# NuEVI.net
KiCad netlist of a schematic drawn in EAGLE
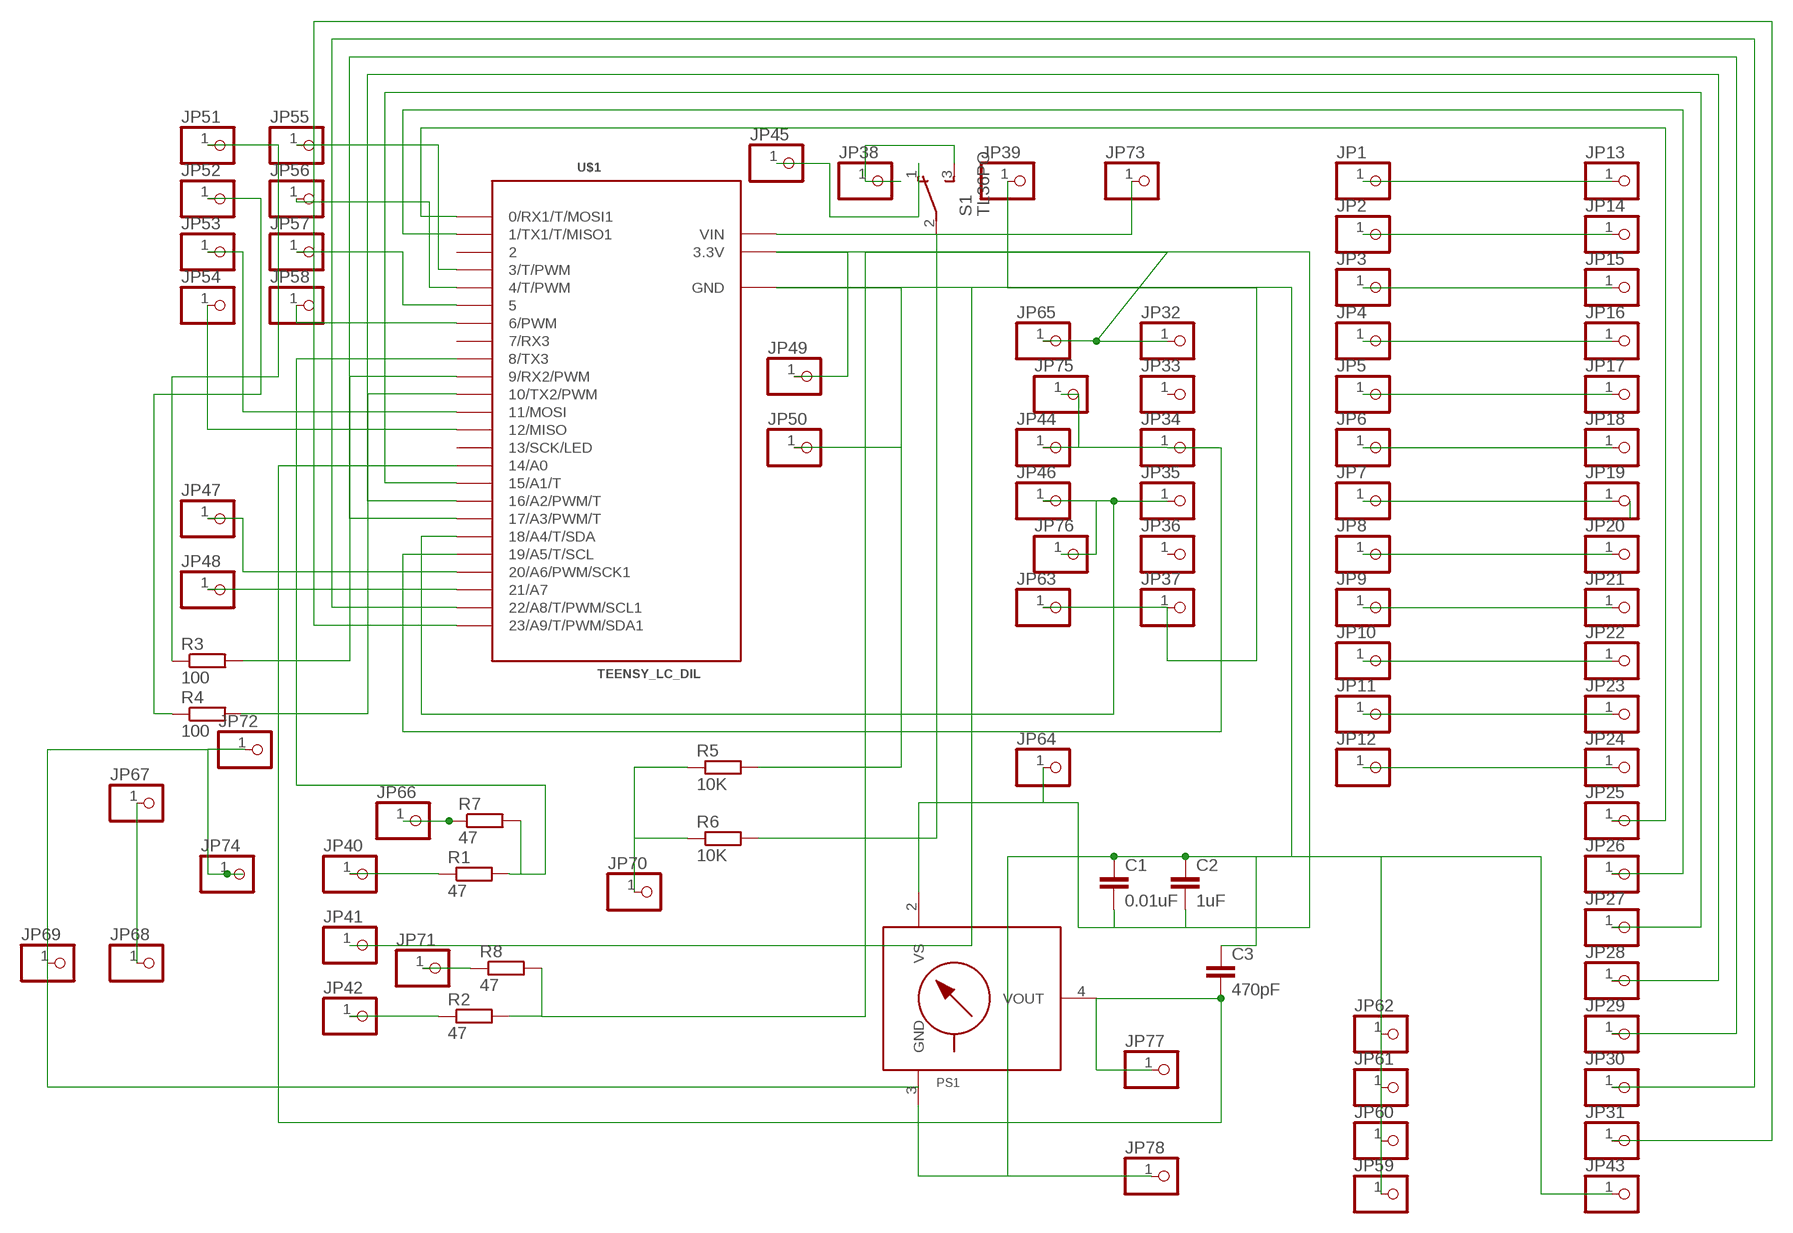
[diagram p0: schematic, sheet 1]

(export (version "E")
  (design (tool "Eeschema 10.0.6"))
  (components
    (comp (ref "C1")
      (value "0.01uF")
      (footprint "eagle-import:C050-024X044")
      (libsource (lib "eagle-import") (part "C-EU050-024X044"))
    )
    (comp (ref "C2")
      (value "1uF")
      (footprint "eagle-import:C050-024X044")
      (libsource (lib "eagle-import") (part "C-EU050-024X044"))
    )
    (comp (ref "C3")
      (value "470pF")
      (footprint "eagle-import:C050-024X044")
      (libsource (lib "eagle-import") (part "C-EU050-024X044"))
    )
    (comp (ref "JP1")
      (value "PINHD-1X1")
      (footprint "eagle-import:1X01")
      (libsource (lib "eagle-import") (part "PINHD-1X1"))
    )
    (comp (ref "JP2")
      (value "PINHD-1X1")
      (footprint "eagle-import:1X01")
      (libsource (lib "eagle-import") (part "PINHD-1X1"))
    )
    (comp (ref "JP3")
      (value "PINHD-1X1")
      (footprint "eagle-import:1X01")
      (libsource (lib "eagle-import") (part "PINHD-1X1"))
    )
    (comp (ref "JP4")
      (value "PINHD-1X1")
      (footprint "eagle-import:1X01")
      (libsource (lib "eagle-import") (part "PINHD-1X1"))
    )
    (comp (ref "JP5")
      (value "PINHD-1X1")
      (footprint "eagle-import:1X01")
      (libsource (lib "eagle-import") (part "PINHD-1X1"))
    )
    (comp (ref "JP6")
      (value "PINHD-1X1")
      (footprint "eagle-import:1X01")
      (libsource (lib "eagle-import") (part "PINHD-1X1"))
    )
    (comp (ref "JP7")
      (value "PINHD-1X1")
      (footprint "eagle-import:1X01")
      (libsource (lib "eagle-import") (part "PINHD-1X1"))
    )
    (comp (ref "JP8")
      (value "PINHD-1X1")
      (footprint "eagle-import:1X01")
      (libsource (lib "eagle-import") (part "PINHD-1X1"))
    )
    (comp (ref "JP9")
      (value "PINHD-1X1")
      (footprint "eagle-import:1X01")
      (libsource (lib "eagle-import") (part "PINHD-1X1"))
    )
    (comp (ref "JP10")
      (value "PINHD-1X1")
      (footprint "eagle-import:1X01")
      (libsource (lib "eagle-import") (part "PINHD-1X1"))
    )
    (comp (ref "JP11")
      (value "PINHD-1X1")
      (footprint "eagle-import:1X01")
      (libsource (lib "eagle-import") (part "PINHD-1X1"))
    )
    (comp (ref "JP12")
      (value "PINHD-1X1")
      (footprint "eagle-import:1X01")
      (libsource (lib "eagle-import") (part "PINHD-1X1"))
    )
    (comp (ref "JP13")
      (value "PINHD-1X1")
      (footprint "eagle-import:1X01")
      (libsource (lib "eagle-import") (part "PINHD-1X1"))
    )
    (comp (ref "JP14")
      (value "PINHD-1X1")
      (footprint "eagle-import:1X01")
      (libsource (lib "eagle-import") (part "PINHD-1X1"))
    )
    (comp (ref "JP15")
      (value "PINHD-1X1")
      (footprint "eagle-import:1X01")
      (libsource (lib "eagle-import") (part "PINHD-1X1"))
    )
    (comp (ref "JP16")
      (value "PINHD-1X1")
      (footprint "eagle-import:1X01")
      (libsource (lib "eagle-import") (part "PINHD-1X1"))
    )
    (comp (ref "JP17")
      (value "PINHD-1X1")
      (footprint "eagle-import:1X01")
      (libsource (lib "eagle-import") (part "PINHD-1X1"))
    )
    (comp (ref "JP18")
      (value "PINHD-1X1")
      (footprint "eagle-import:1X01")
      (libsource (lib "eagle-import") (part "PINHD-1X1"))
    )
    (comp (ref "JP19")
      (value "PINHD-1X1")
      (footprint "eagle-import:1X01")
      (libsource (lib "eagle-import") (part "PINHD-1X1"))
    )
    (comp (ref "JP20")
      (value "PINHD-1X1")
      (footprint "eagle-import:1X01")
      (libsource (lib "eagle-import") (part "PINHD-1X1"))
    )
    (comp (ref "JP21")
      (value "PINHD-1X1")
      (footprint "eagle-import:1X01")
      (libsource (lib "eagle-import") (part "PINHD-1X1"))
    )
    (comp (ref "JP22")
      (value "PINHD-1X1")
      (footprint "eagle-import:1X01")
      (libsource (lib "eagle-import") (part "PINHD-1X1"))
    )
    (comp (ref "JP23")
      (value "PINHD-1X1")
      (footprint "eagle-import:1X01")
      (libsource (lib "eagle-import") (part "PINHD-1X1"))
    )
    (comp (ref "JP24")
      (value "PINHD-1X1")
      (footprint "eagle-import:1X01")
      (libsource (lib "eagle-import") (part "PINHD-1X1"))
    )
    (comp (ref "JP25")
      (value "PINHD-1X1")
      (footprint "eagle-import:1X01")
      (libsource (lib "eagle-import") (part "PINHD-1X1"))
    )
    (comp (ref "JP26")
      (value "PINHD-1X1")
      (footprint "eagle-import:1X01")
      (libsource (lib "eagle-import") (part "PINHD-1X1"))
    )
    (comp (ref "JP27")
      (value "PINHD-1X1")
      (footprint "eagle-import:1X01")
      (libsource (lib "eagle-import") (part "PINHD-1X1"))
    )
    (comp (ref "JP28")
      (value "PINHD-1X1")
      (footprint "eagle-import:1X01")
      (libsource (lib "eagle-import") (part "PINHD-1X1"))
    )
    (comp (ref "JP29")
      (value "PINHD-1X1")
      (footprint "eagle-import:1X01")
      (libsource (lib "eagle-import") (part "PINHD-1X1"))
    )
    (comp (ref "JP30")
      (value "PINHD-1X1")
      (footprint "eagle-import:1X01")
      (libsource (lib "eagle-import") (part "PINHD-1X1"))
    )
    (comp (ref "JP31")
      (value "PINHD-1X1")
      (footprint "eagle-import:1X01")
      (libsource (lib "eagle-import") (part "PINHD-1X1"))
    )
    (comp (ref "JP32")
      (value "PINHD-1X1")
      (footprint "eagle-import:1X01")
      (libsource (lib "eagle-import") (part "PINHD-1X1"))
    )
    (comp (ref "JP33")
      (value "PINHD-1X1")
      (footprint "eagle-import:1X01")
      (libsource (lib "eagle-import") (part "PINHD-1X1"))
    )
    (comp (ref "JP34")
      (value "PINHD-1X1")
      (footprint "eagle-import:1X01")
      (libsource (lib "eagle-import") (part "PINHD-1X1"))
    )
    (comp (ref "JP35")
      (value "PINHD-1X1")
      (footprint "eagle-import:1X01")
      (libsource (lib "eagle-import") (part "PINHD-1X1"))
    )
    (comp (ref "JP36")
      (value "PINHD-1X1")
      (footprint "eagle-import:1X01")
      (libsource (lib "eagle-import") (part "PINHD-1X1"))
    )
    (comp (ref "JP37")
      (value "PINHD-1X1")
      (footprint "eagle-import:1X01")
      (libsource (lib "eagle-import") (part "PINHD-1X1"))
    )
    (comp (ref "JP38")
      (value "PINHD-1X1")
      (footprint "eagle-import:1X01")
      (libsource (lib "eagle-import") (part "PINHD-1X1"))
    )
    (comp (ref "JP39")
      (value "PINHD-1X1")
      (footprint "eagle-import:1X01")
      (libsource (lib "eagle-import") (part "PINHD-1X1"))
    )
    (comp (ref "JP40")
      (value "PINHD-1X1")
      (footprint "eagle-import:1X01")
      (libsource (lib "eagle-import") (part "PINHD-1X1"))
    )
    (comp (ref "JP41")
      (value "PINHD-1X1")
      (footprint "eagle-import:1X01")
      (libsource (lib "eagle-import") (part "PINHD-1X1"))
    )
    (comp (ref "JP42")
      (value "PINHD-1X1")
      (footprint "eagle-import:1X01")
      (libsource (lib "eagle-import") (part "PINHD-1X1"))
    )
    (comp (ref "JP43")
      (value "PINHD-1X1")
      (footprint "eagle-import:1X01")
      (libsource (lib "eagle-import") (part "PINHD-1X1"))
    )
    (comp (ref "JP44")
      (value "PINHD-1X1")
      (footprint "eagle-import:1X01")
      (libsource (lib "eagle-import") (part "PINHD-1X1"))
    )
    (comp (ref "JP45")
      (value "PINHD-1X1")
      (footprint "eagle-import:1X01")
      (libsource (lib "eagle-import") (part "PINHD-1X1"))
    )
    (comp (ref "JP46")
      (value "PINHD-1X1")
      (footprint "eagle-import:1X01")
      (libsource (lib "eagle-import") (part "PINHD-1X1"))
    )
    (comp (ref "JP47")
      (value "PINHD-1X1")
      (footprint "eagle-import:1X01")
      (libsource (lib "eagle-import") (part "PINHD-1X1"))
    )
    (comp (ref "JP48")
      (value "PINHD-1X1")
      (footprint "eagle-import:1X01")
      (libsource (lib "eagle-import") (part "PINHD-1X1"))
    )
    (comp (ref "JP49")
      (value "PINHD-1X1")
      (footprint "eagle-import:1X01")
      (libsource (lib "eagle-import") (part "PINHD-1X1"))
    )
    (comp (ref "JP50")
      (value "PINHD-1X1")
      (footprint "eagle-import:1X01")
      (libsource (lib "eagle-import") (part "PINHD-1X1"))
    )
    (comp (ref "JP51")
      (value "PINHD-1X1")
      (footprint "eagle-import:1X01")
      (libsource (lib "eagle-import") (part "PINHD-1X1"))
    )
    (comp (ref "JP52")
      (value "PINHD-1X1")
      (footprint "eagle-import:1X01")
      (libsource (lib "eagle-import") (part "PINHD-1X1"))
    )
    (comp (ref "JP53")
      (value "PINHD-1X1")
      (footprint "eagle-import:1X01")
      (libsource (lib "eagle-import") (part "PINHD-1X1"))
    )
    (comp (ref "JP54")
      (value "PINHD-1X1")
      (footprint "eagle-import:1X01")
      (libsource (lib "eagle-import") (part "PINHD-1X1"))
    )
    (comp (ref "JP55")
      (value "PINHD-1X1")
      (footprint "eagle-import:1X01")
      (libsource (lib "eagle-import") (part "PINHD-1X1"))
    )
    (comp (ref "JP56")
      (value "PINHD-1X1")
      (footprint "eagle-import:1X01")
      (libsource (lib "eagle-import") (part "PINHD-1X1"))
    )
    (comp (ref "JP57")
      (value "PINHD-1X1")
      (footprint "eagle-import:1X01")
      (libsource (lib "eagle-import") (part "PINHD-1X1"))
    )
    (comp (ref "JP58")
      (value "PINHD-1X1")
      (footprint "eagle-import:1X01")
      (libsource (lib "eagle-import") (part "PINHD-1X1"))
    )
    (comp (ref "JP59")
      (value "PINHD-1X1")
      (footprint "eagle-import:1X01")
      (libsource (lib "eagle-import") (part "PINHD-1X1"))
    )
    (comp (ref "JP60")
      (value "PINHD-1X1")
      (footprint "eagle-import:1X01")
      (libsource (lib "eagle-import") (part "PINHD-1X1"))
    )
    (comp (ref "JP61")
      (value "PINHD-1X1")
      (footprint "eagle-import:1X01")
      (libsource (lib "eagle-import") (part "PINHD-1X1"))
    )
    (comp (ref "JP62")
      (value "PINHD-1X1")
      (footprint "eagle-import:1X01")
      (libsource (lib "eagle-import") (part "PINHD-1X1"))
    )
    (comp (ref "JP63")
      (value "PINHD-1X1")
      (footprint "eagle-import:1X01")
      (libsource (lib "eagle-import") (part "PINHD-1X1"))
    )
    (comp (ref "JP64")
      (value "PINHD-1X1")
      (footprint "eagle-import:1X01")
      (libsource (lib "eagle-import") (part "PINHD-1X1"))
    )
    (comp (ref "JP65")
      (value "PINHD-1X1")
      (footprint "eagle-import:1X01")
      (libsource (lib "eagle-import") (part "PINHD-1X1"))
    )
    (comp (ref "JP66")
      (value "PINHD-1X1")
      (footprint "eagle-import:1X01")
      (libsource (lib "eagle-import") (part "PINHD-1X1"))
    )
    (comp (ref "JP67")
      (value "PINHD-1X1")
      (footprint "eagle-import:1X01")
      (libsource (lib "eagle-import") (part "PINHD-1X1"))
    )
    (comp (ref "JP68")
      (value "PINHD-1X1")
      (footprint "eagle-import:1X01")
      (libsource (lib "eagle-import") (part "PINHD-1X1"))
    )
    (comp (ref "JP69")
      (value "PINHD-1X1")
      (footprint "eagle-import:1X01")
      (libsource (lib "eagle-import") (part "PINHD-1X1"))
    )
    (comp (ref "JP70")
      (value "PINHD-1X1")
      (footprint "eagle-import:1X01")
      (libsource (lib "eagle-import") (part "PINHD-1X1"))
    )
    (comp (ref "JP71")
      (value "PINHD-1X1")
      (footprint "eagle-import:1X01")
      (libsource (lib "eagle-import") (part "PINHD-1X1"))
    )
    (comp (ref "JP72")
      (value "PINHD-1X1")
      (footprint "eagle-import:1X01")
      (libsource (lib "eagle-import") (part "PINHD-1X1"))
    )
    (comp (ref "JP73")
      (value "PINHD-1X1")
      (footprint "eagle-import:1X01")
      (libsource (lib "eagle-import") (part "PINHD-1X1"))
    )
    (comp (ref "JP74")
      (value "PINHD-1X1")
      (footprint "eagle-import:1X01")
      (libsource (lib "eagle-import") (part "PINHD-1X1"))
    )
    (comp (ref "JP75")
      (value "PINHD-1X1")
      (footprint "eagle-import:1X01")
      (libsource (lib "eagle-import") (part "PINHD-1X1"))
    )
    (comp (ref "JP76")
      (value "PINHD-1X1")
      (footprint "eagle-import:1X01")
      (libsource (lib "eagle-import") (part "PINHD-1X1"))
    )
    (comp (ref "JP77")
      (value "PINHD-1X1")
      (footprint "eagle-import:1X01")
      (libsource (lib "eagle-import") (part "PINHD-1X1"))
    )
    (comp (ref "JP78")
      (value "PINHD-1X1")
      (footprint "eagle-import:1X01")
      (libsource (lib "eagle-import") (part "PINHD-1X1"))
    )
    (comp (ref "PS1")
      (value "MPX-1369")
      (footprint "eagle-import:1369")
      (libsource (lib "eagle-import") (part "MPX-1369"))
    )
    (comp (ref "R1")
      (value "47")
      (footprint "eagle-import:0207_7")
      (libsource (lib "eagle-import") (part "R-EU_0207/7"))
    )
    (comp (ref "R2")
      (value "47")
      (footprint "eagle-import:0207_7")
      (libsource (lib "eagle-import") (part "R-EU_0207/7"))
    )
    (comp (ref "R3")
      (value "100")
      (footprint "eagle-import:0207_7")
      (libsource (lib "eagle-import") (part "R-EU_0207/7"))
    )
    (comp (ref "R4")
      (value "100")
      (footprint "eagle-import:0207_7")
      (libsource (lib "eagle-import") (part "R-EU_0207/7"))
    )
    (comp (ref "R5")
      (value "10K")
      (footprint "eagle-import:0207_7")
      (libsource (lib "eagle-import") (part "R-EU_0207/7"))
    )
    (comp (ref "R6")
      (value "10K")
      (footprint "eagle-import:0207_7")
      (libsource (lib "eagle-import") (part "R-EU_0207/7"))
    )
    (comp (ref "R7")
      (value "47")
      (footprint "eagle-import:0207_7")
      (libsource (lib "eagle-import") (part "R-EU_0207/7"))
    )
    (comp (ref "R8")
      (value "47")
      (footprint "eagle-import:0207_7")
      (libsource (lib "eagle-import") (part "R-EU_0207/7"))
    )
    (comp (ref "S1")
      (value "TL36PO")
      (footprint "eagle-import:TL3XPO")
      (libsource (lib "eagle-import") (part "TL36PO"))
    )
    (comp (ref "U$1")
      (value "TEENSY_LC_DIL")
      (footprint "eagle-import:TEENSY_3.0-3.2&LC_DIL")
      (libsource (lib "eagle-import") (part "TEENSY_LC_DIL"))
    )
  )
  (nets
    (net (code "1") (name "/GND") (class "Default")
      (node (ref "C1") (pin "1") (pinfunction "1_1") (pintype "passive"))
      (node (ref "C2") (pin "1") (pinfunction "1_1") (pintype "passive"))
      (node (ref "C3") (pin "1") (pinfunction "1_1") (pintype "passive"))
      (node (ref "JP37") (pin "1") (pinfunction "1_1") (pintype "passive"))
      (node (ref "JP39") (pin "1") (pinfunction "1_1") (pintype "passive"))
      (node (ref "JP41") (pin "1") (pinfunction "1_1") (pintype "passive"))
      (node (ref "JP43") (pin "1") (pinfunction "1_1") (pintype "passive"))
      (node (ref "JP50") (pin "1") (pinfunction "1_1") (pintype "passive"))
      (node (ref "JP59") (pin "1") (pinfunction "1_1") (pintype "passive"))
      (node (ref "JP60") (pin "1") (pinfunction "1_1") (pintype "passive"))
      (node (ref "JP61") (pin "1") (pinfunction "1_1") (pintype "passive"))
      (node (ref "JP62") (pin "1") (pinfunction "1_1") (pintype "passive"))
      (node (ref "JP63") (pin "1") (pinfunction "1_1") (pintype "passive"))
      (node (ref "JP69") (pin "1") (pinfunction "1_1") (pintype "passive"))
      (node (ref "JP72") (pin "1") (pinfunction "1_1") (pintype "passive"))
      (node (ref "JP74") (pin "1") (pinfunction "1_1") (pintype "passive"))
      (node (ref "JP78") (pin "1") (pinfunction "1_1") (pintype "passive"))
      (node (ref "PS1") (pin "3") (pinfunction "GND_3") (pintype "power_in"))
      (node (ref "R5") (pin "2") (pinfunction "2_2") (pintype "passive"))
      (node (ref "U$1") (pin "AGND") (pinfunction "GND_AGND") (pintype "power_in"))
      (node (ref "U$1") (pin "GND") (pinfunction "GND_GND") (pintype "power_in"))
    )
    (net (code "2") (name "Net-(JP1-Pad1)") (class "Default")
      (node (ref "JP1") (pin "1") (pinfunction "1_1") (pintype "passive"))
      (node (ref "JP13") (pin "1") (pinfunction "1_1") (pintype "passive"))
    )
    (net (code "3") (name "Net-(JP10-Pad1)") (class "Default")
      (node (ref "JP10") (pin "1") (pinfunction "1_1") (pintype "passive"))
      (node (ref "JP22") (pin "1") (pinfunction "1_1") (pintype "passive"))
    )
    (net (code "4") (name "Net-(JP11-Pad1)") (class "Default")
      (node (ref "JP11") (pin "1") (pinfunction "1_1") (pintype "passive"))
      (node (ref "JP23") (pin "1") (pinfunction "1_1") (pintype "passive"))
    )
    (net (code "5") (name "Net-(JP12-Pad1)") (class "Default")
      (node (ref "JP12") (pin "1") (pinfunction "1_1") (pintype "passive"))
      (node (ref "JP24") (pin "1") (pinfunction "1_1") (pintype "passive"))
    )
    (net (code "6") (name "Net-(JP14-Pad1)") (class "Default")
      (node (ref "JP14") (pin "1") (pinfunction "1_1") (pintype "passive"))
      (node (ref "JP2") (pin "1") (pinfunction "1_1") (pintype "passive"))
    )
    (net (code "7") (name "Net-(JP15-Pad1)") (class "Default")
      (node (ref "JP15") (pin "1") (pinfunction "1_1") (pintype "passive"))
      (node (ref "JP3") (pin "1") (pinfunction "1_1") (pintype "passive"))
    )
    (net (code "8") (name "Net-(JP16-Pad1)") (class "Default")
      (node (ref "JP16") (pin "1") (pinfunction "1_1") (pintype "passive"))
      (node (ref "JP4") (pin "1") (pinfunction "1_1") (pintype "passive"))
    )
    (net (code "9") (name "Net-(JP17-Pad1)") (class "Default")
      (node (ref "JP17") (pin "1") (pinfunction "1_1") (pintype "passive"))
      (node (ref "JP5") (pin "1") (pinfunction "1_1") (pintype "passive"))
    )
    (net (code "10") (name "Net-(JP18-Pad1)") (class "Default")
      (node (ref "JP18") (pin "1") (pinfunction "1_1") (pintype "passive"))
      (node (ref "JP6") (pin "1") (pinfunction "1_1") (pintype "passive"))
    )
    (net (code "11") (name "Net-(JP19-Pad1)") (class "Default")
      (node (ref "JP19") (pin "1") (pinfunction "1_1") (pintype "passive"))
      (node (ref "JP7") (pin "1") (pinfunction "1_1") (pintype "passive"))
    )
    (net (code "12") (name "Net-(JP20-Pad1)") (class "Default")
      (node (ref "JP20") (pin "1") (pinfunction "1_1") (pintype "passive"))
      (node (ref "JP8") (pin "1") (pinfunction "1_1") (pintype "passive"))
    )
    (net (code "13") (name "Net-(JP21-Pad1)") (class "Default")
      (node (ref "JP21") (pin "1") (pinfunction "1_1") (pintype "passive"))
      (node (ref "JP9") (pin "1") (pinfunction "1_1") (pintype "passive"))
    )
    (net (code "14") (name "Net-(JP40-Pad1)") (class "Default")
      (node (ref "JP40") (pin "1") (pinfunction "1_1") (pintype "passive"))
      (node (ref "R1") (pin "1") (pinfunction "1_1") (pintype "passive"))
    )
    (net (code "15") (name "Net-(JP42-Pad1)") (class "Default")
      (node (ref "JP42") (pin "1") (pinfunction "1_1") (pintype "passive"))
      (node (ref "R2") (pin "1") (pinfunction "1_1") (pintype "passive"))
    )
    (net (code "16") (name "Net-(JP48-Pad1)") (class "Default")
      (node (ref "JP48") (pin "1") (pinfunction "1_1") (pintype "passive"))
      (node (ref "U$1") (pin "21/A7") (pinfunction "21/A7_21/A7") (pintype "bidirectional"))
    )
    (net (code "17") (name "Net-(JP51-Pad1)") (class "Default")
      (node (ref "JP51") (pin "1") (pinfunction "1_1") (pintype "passive"))
      (node (ref "R3") (pin "1") (pinfunction "1_1") (pintype "passive"))
    )
    (net (code "18") (name "Net-(JP52-Pad1)") (class "Default")
      (node (ref "JP52") (pin "1") (pinfunction "1_1") (pintype "passive"))
      (node (ref "R4") (pin "1") (pinfunction "1_1") (pintype "passive"))
    )
    (net (code "19") (name "Net-(JP57-Pad1)") (class "Default")
      (node (ref "JP57") (pin "1") (pinfunction "1_1") (pintype "passive"))
      (node (ref "U$1") (pin "5") (pinfunction "5_5") (pintype "bidirectional"))
    )
    (net (code "20") (name "Net-(JP66-Pad1)") (class "Default")
      (node (ref "JP66") (pin "1") (pinfunction "1_1") (pintype "passive"))
      (node (ref "R7") (pin "1") (pinfunction "1_1") (pintype "passive"))
    )
    (net (code "21") (name "Net-(JP67-Pad1)") (class "Default")
      (node (ref "JP67") (pin "1") (pinfunction "1_1") (pintype "passive"))
      (node (ref "JP68") (pin "1") (pinfunction "1_1") (pintype "passive"))
    )
    (net (code "22") (name "Net-(JP70-Pad1)") (class "Default")
      (node (ref "JP70") (pin "1") (pinfunction "1_1") (pintype "passive"))
      (node (ref "R5") (pin "1") (pinfunction "1_1") (pintype "passive"))
      (node (ref "R6") (pin "1") (pinfunction "1_1") (pintype "passive"))
    )
    (net (code "23") (name "Net-(JP71-Pad1)") (class "Default")
      (node (ref "JP71") (pin "1") (pinfunction "1_1") (pintype "passive"))
      (node (ref "R8") (pin "1") (pinfunction "1_1") (pintype "passive"))
    )
    (net (code "24") (name "Net-(PS1-VOUT)") (class "Default")
      (node (ref "C3") (pin "2") (pinfunction "2_2") (pintype "passive"))
      (node (ref "JP77") (pin "1") (pinfunction "1_1") (pintype "passive"))
      (node (ref "PS1") (pin "4") (pinfunction "VOUT_4") (pintype "output"))
      (node (ref "U$1") (pin "14/A0") (pinfunction "14/A0_14/A0") (pintype "bidirectional"))
    )
    (net (code "25") (name "Net-(PS1-VS)") (class "Default")
      (node (ref "C1") (pin "2") (pinfunction "2_2") (pintype "passive"))
      (node (ref "C2") (pin "2") (pinfunction "2_2") (pintype "passive"))
      (node (ref "JP32") (pin "1") (pinfunction "1_1") (pintype "passive"))
      (node (ref "JP49") (pin "1") (pinfunction "1_1") (pintype "passive"))
      (node (ref "JP64") (pin "1") (pinfunction "1_1") (pintype "passive"))
      (node (ref "JP65") (pin "1") (pinfunction "1_1") (pintype "passive"))
      (node (ref "PS1") (pin "2") (pinfunction "VS_2") (pintype "power_in"))
      (node (ref "R2") (pin "2") (pinfunction "2_2") (pintype "passive"))
      (node (ref "R8") (pin "2") (pinfunction "2_2") (pintype "passive"))
      (node (ref "U$1") (pin "3.3V") (pinfunction "3.3V_3.3V") (pintype "power_in"))
    )
    (net (code "26") (name "Net-(S1-O)") (class "Default")
      (node (ref "JP45") (pin "1") (pinfunction "1_1") (pintype "passive"))
      (node (ref "S1") (pin "1") (pinfunction "O_1") (pintype "passive"))
    )
    (net (code "27") (name "Net-(S1-P)") (class "Default")
      (node (ref "JP73") (pin "1") (pinfunction "1_1") (pintype "passive"))
      (node (ref "R6") (pin "2") (pinfunction "2_2") (pintype "passive"))
      (node (ref "S1") (pin "2") (pinfunction "P_2") (pintype "passive"))
      (node (ref "U$1") (pin "VIN") (pinfunction "VIN_VIN") (pintype "power_in"))
    )
    (net (code "28") (name "Net-(S1-S)") (class "Default")
      (node (ref "JP38") (pin "1") (pinfunction "1_1") (pintype "passive"))
      (node (ref "S1") (pin "3") (pinfunction "S_3") (pintype "passive"))
    )
    (net (code "29") (name "Net-(U$1-0{slash}RX1{slash}T{slash}MOSI1)") (class "Default")
      (node (ref "JP25") (pin "1") (pinfunction "1_1") (pintype "passive"))
      (node (ref "U$1") (pin "0") (pinfunction "0/RX1/T/MOSI1_0") (pintype "bidirectional"))
    )
    (net (code "30") (name "Net-(U$1-1{slash}TX1{slash}T{slash}MISO1)") (class "Default")
      (node (ref "JP26") (pin "1") (pinfunction "1_1") (pintype "passive"))
      (node (ref "U$1") (pin "1") (pinfunction "1/TX1/T/MISO1_1") (pintype "bidirectional"))
    )
    (net (code "31") (name "Net-(U$1-3{slash}T{slash}PWM)") (class "Default")
      (node (ref "JP55") (pin "1") (pinfunction "1_1") (pintype "passive"))
      (node (ref "U$1") (pin "3") (pinfunction "3/T/PWM_3") (pintype "bidirectional"))
    )
    (net (code "32") (name "Net-(U$1-4{slash}T{slash}PWM)") (class "Default")
      (node (ref "JP56") (pin "1") (pinfunction "1_1") (pintype "passive"))
      (node (ref "U$1") (pin "4") (pinfunction "4/T/PWM_4") (pintype "bidirectional"))
    )
    (net (code "33") (name "Net-(U$1-6{slash}PWM)") (class "Default")
      (node (ref "JP58") (pin "1") (pinfunction "1_1") (pintype "passive"))
      (node (ref "U$1") (pin "6") (pinfunction "6/PWM_6") (pintype "bidirectional"))
    )
    (net (code "34") (name "Net-(U$1-8{slash}TX3)") (class "Default")
      (node (ref "R1") (pin "2") (pinfunction "2_2") (pintype "passive"))
      (node (ref "R7") (pin "2") (pinfunction "2_2") (pintype "passive"))
      (node (ref "U$1") (pin "8") (pinfunction "8/TX3_8") (pintype "bidirectional"))
    )
    (net (code "35") (name "Net-(U$1-9{slash}RX2{slash}PWM)") (class "Default")
      (node (ref "R3") (pin "2") (pinfunction "2_2") (pintype "passive"))
      (node (ref "U$1") (pin "9") (pinfunction "9/RX2/PWM_9") (pintype "bidirectional"))
    )
    (net (code "36") (name "Net-(U$1-10{slash}TX2{slash}PWM)") (class "Default")
      (node (ref "R4") (pin "2") (pinfunction "2_2") (pintype "passive"))
      (node (ref "U$1") (pin "10") (pinfunction "10/TX2/PWM_10") (pintype "bidirectional"))
    )
    (net (code "37") (name "Net-(U$1-11{slash}MOSI)") (class "Default")
      (node (ref "JP53") (pin "1") (pinfunction "1_1") (pintype "passive"))
      (node (ref "U$1") (pin "11") (pinfunction "11/MOSI_11") (pintype "bidirectional"))
    )
    (net (code "38") (name "Net-(U$1-12{slash}MISO)") (class "Default")
      (node (ref "JP54") (pin "1") (pinfunction "1_1") (pintype "passive"))
      (node (ref "U$1") (pin "12") (pinfunction "12/MISO_12") (pintype "bidirectional"))
    )
    (net (code "39") (name "Net-(U$1-15{slash}A1{slash}T)") (class "Default")
      (node (ref "JP27") (pin "1") (pinfunction "1_1") (pintype "passive"))
      (node (ref "U$1") (pin "15/A1") (pinfunction "15/A1/T_15/A1") (pintype "bidirectional"))
    )
    (net (code "40") (name "Net-(U$1-16{slash}A2{slash}PWM{slash}T)") (class "Default")
      (node (ref "JP28") (pin "1") (pinfunction "1_1") (pintype "passive"))
      (node (ref "U$1") (pin "16/A2") (pinfunction "16/A2/PWM/T_16/A2") (pintype "bidirectional"))
    )
    (net (code "41") (name "Net-(U$1-17{slash}A3{slash}PWM{slash}T)") (class "Default")
      (node (ref "JP29") (pin "1") (pinfunction "1_1") (pintype "passive"))
      (node (ref "U$1") (pin "17/A3") (pinfunction "17/A3/PWM/T_17/A3") (pintype "bidirectional"))
    )
    (net (code "42") (name "Net-(U$1-18{slash}A4{slash}T{slash}SDA)") (class "Default")
      (node (ref "JP35") (pin "1") (pinfunction "1_1") (pintype "passive"))
      (node (ref "JP46") (pin "1") (pinfunction "1_1") (pintype "passive"))
      (node (ref "JP76") (pin "1") (pinfunction "1_1") (pintype "passive"))
      (node (ref "U$1") (pin "18/A4") (pinfunction "18/A4/T/SDA_18/A4") (pintype "bidirectional"))
    )
    (net (code "43") (name "Net-(U$1-19{slash}A5{slash}T{slash}SCL)") (class "Default")
      (node (ref "JP34") (pin "1") (pinfunction "1_1") (pintype "passive"))
      (node (ref "JP44") (pin "1") (pinfunction "1_1") (pintype "passive"))
      (node (ref "JP75") (pin "1") (pinfunction "1_1") (pintype "passive"))
      (node (ref "U$1") (pin "19/A5") (pinfunction "19/A5/T/SCL_19/A5") (pintype "bidirectional"))
    )
    (net (code "44") (name "Net-(U$1-20{slash}A6{slash}PWM{slash}SCK1)") (class "Default")
      (node (ref "JP47") (pin "1") (pinfunction "1_1") (pintype "passive"))
      (node (ref "U$1") (pin "20/A6") (pinfunction "20/A6/PWM/SCK1_20/A6") (pintype "bidirectional"))
    )
    (net (code "45") (name "Net-(U$1-22{slash}A8{slash}T{slash}PWM{slash}SCL1)") (class "Default")
      (node (ref "JP30") (pin "1") (pinfunction "1_1") (pintype "passive"))
      (node (ref "U$1") (pin "22/A8") (pinfunction "22/A8/T/PWM/SCL1_22/A8") (pintype "bidirectional"))
    )
    (net (code "46") (name "Net-(U$1-23{slash}A9{slash}T{slash}PWM{slash}SDA1)") (class "Default")
      (node (ref "JP31") (pin "1") (pinfunction "1_1") (pintype "passive"))
      (node (ref "U$1") (pin "23/A9") (pinfunction "23/A9/T/PWM/SDA1_23/A9") (pintype "bidirectional"))
    )
    (net (code "47") (name "unconnected-(JP33-Pad1)") (class "Default")
      (node (ref "JP33") (pin "1") (pinfunction "1_1") (pintype "passive"))
    )
    (net (code "48") (name "unconnected-(JP36-Pad1)") (class "Default")
      (node (ref "JP36") (pin "1") (pinfunction "1_1") (pintype "passive"))
    )
    (net (code "49") (name "unconnected-(PS1-NC-Pad1)") (class "Default")
      (node (ref "PS1") (pin "1") (pinfunction "NC_1") (pintype "no_connect"))
    )
    (net (code "50") (name "unconnected-(PS1-NC-Pad5)") (class "Default")
      (node (ref "PS1") (pin "5") (pinfunction "NC_5") (pintype "no_connect"))
    )
    (net (code "51") (name "unconnected-(PS1-NC-Pad6)") (class "Default")
      (node (ref "PS1") (pin "6") (pinfunction "NC_6") (pintype "no_connect"))
    )
    (net (code "52") (name "unconnected-(U$1-7{slash}RX3-Pad7)") (class "Default")
      (node (ref "U$1") (pin "7") (pinfunction "7/RX3_7") (pintype "bidirectional"))
    )
    (net (code "53") (name "unconnected-(U$1-13{slash}SCK{slash}LED-Pad13)") (class "Default")
      (node (ref "U$1") (pin "13") (pinfunction "13/SCK/LED_13") (pintype "bidirectional"))
    )
    (net (code "54") (name "unconnected-(U$1-Pad2)") (class "Default")
      (node (ref "U$1") (pin "2") (pinfunction "2_2") (pintype "bidirectional"))
    )
  )
)
